# supply.net
KiCad netlist of a schematic drawn in Altium Designer
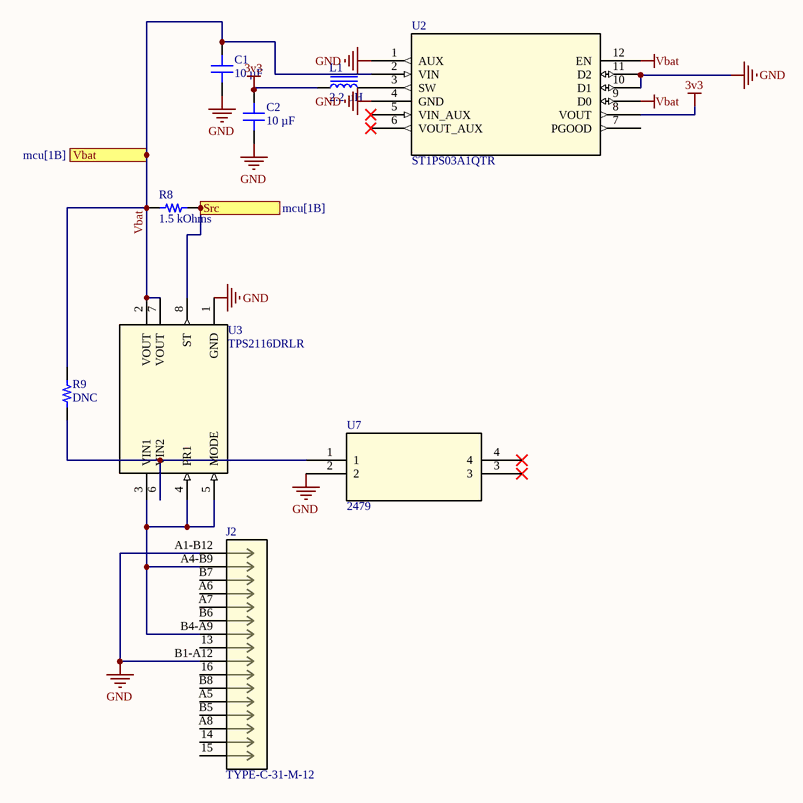
[diagram p0: supply.SchDoc]

(export (version "E")
  (design (tool "Eeschema 10.0.6"))
  (components
    (comp (ref "C1")
      (value "10 µF")
      (footprint "CAP 0402_1005")
      (description "CAP CER 0.1UF 4V X5R 0402")
      (fields (field (name "PART NUMBER") "C0402C104K7PAC7867") (field (name "MANUFACTURER") "KEMET"))
      (libsource (lib "Celestial Altium Library - altium_library") (part "Capacitor"))
    )
    (comp (ref "C2")
      (value "10 µF")
      (footprint "CAP 0402_1005")
      (description "CAP CER 0.1UF 4V X5R 0402")
      (fields (field (name "PART NUMBER") "C0402C104K7PAC7867") (field (name "MANUFACTURER") "KEMET"))
      (libsource (lib "Celestial Altium Library - altium_library") (part "Capacitor"))
    )
    (comp (ref "J2")
      (value "TYPE-C-31-M-12")
      (footprint "CONN12_C-31-M-12_HRO")
      (description "No Description Available")
      (libsource (lib "TYPE-C-31-M-12") (part "TYPE-C-31-M-12"))
    )
    (comp (ref "L1")
      (value "2.2 µH")
      (footprint "TDK VLS201612CX")
      (description "FIXED IND 6.8UH 930MA 368MOHM SM")
      (fields
        (field (name "PART NUMBER") "VLS201612CX-6R8M-1")
        (field (name "MANUFACTURER") "TDK Corporation")
      )
      (libsource (lib "Celestial Altium Library - altium_library") (part "Inductor"))
    )
    (comp (ref "R8")
      (value "1.5 kOhms")
      (footprint "RES 0402_1005")
      (description "RES 1.5K OHM 0.05% 1/10W 0402")
      (fields
        (field (name "PART NUMBER") "ERA-2VRW1501X")
        (field (name "MANUFACTURER") "Panasonic Electronic Components")
      )
      (libsource (lib "Celestial Altium Library - altium_library") (part "Resistor"))
    )
    (comp (ref "R9")
      (value "DNC")
      (footprint "RES 0402_1005")
      (description "RES 1.5K OHM 0.05% 1/10W 0402")
      (fields
        (field (name "PART NUMBER") "ERA-2VRW1501X")
        (field (name "MANUFACTURER") "Panasonic Electronic Components")
      )
      (libsource (lib "Celestial Altium Library - altium_library") (part "Resistor"))
    )
    (comp (ref "U2")
      (value "ST1PS03A1QTR")
      (footprint "TQFN12_2X1P7_STM")
      (description "No Description Available")
      (libsource (lib "ST1PS03A1QTR") (part "ST1PS03A1QTR"))
    )
    (comp (ref "U3")
      (value "TPS2116DRLR")
      (footprint "DRL0008A-MFG")
      (description "No Description Available")
      (libsource (lib "TPS2116DRLR") (part "TPS2116DRLR"))
    )
    (comp (ref "U7")
      (value "2479")
      (footprint "2479PCB_37P49X52P63_KEY")
      (description "No Description Available")
      (libsource (lib "2479") (part "2479"))
    )
  )
  (nets
    (net (code "1") (name "/Src") (class "Default")
      (node (ref "R8") (pin "1") (pinfunction "1_1") (pintype "passive"))
      (node (ref "U3") (pin "8") (pinfunction "ST_8") (pintype "output"))
    )
    (net (code "2") (name "3v3") (class "Default")
      (node (ref "C2") (pin "1") (pinfunction "1_1") (pintype "passive"))
      (node (ref "L1") (pin "1") (pinfunction "1_1") (pintype "passive"))
      (node (ref "U2") (pin "8") (pinfunction "VOUT_8") (pintype "output"))
    )
    (net (code "3") (name "GND") (class "Default")
      (node (ref "C1") (pin "2") (pinfunction "2_2") (pintype "passive"))
      (node (ref "C2") (pin "2") (pinfunction "2_2") (pintype "passive"))
      (node (ref "J2") (pin "A1-B12") (pinfunction "A1-B12_A1-B12") (pintype "passive"))
      (node (ref "J2") (pin "B1-A12") (pinfunction "B1-A12_B1-A12") (pintype "passive"))
      (node (ref "U2") (pin "1") (pinfunction "AUX_1") (pintype "output"))
      (node (ref "U2") (pin "10") (pinfunction "D1_10") (pintype "bidirectional"))
      (node (ref "U2") (pin "11") (pinfunction "D2_11") (pintype "bidirectional"))
      (node (ref "U2") (pin "4") (pinfunction "GND_4") (pintype "power_in"))
      (node (ref "U3") (pin "1") (pinfunction "GND_1") (pintype "power_in"))
      (node (ref "U7") (pin "2") (pinfunction "2_2") (pintype "passive"))
    )
    (net (code "4") (name "Net-(U2-SW)") (class "Default")
      (node (ref "L1") (pin "2") (pinfunction "2_2") (pintype "passive"))
      (node (ref "U2") (pin "3") (pinfunction "SW_3") (pintype "output"))
    )
    (net (code "5") (name "Net-(U3-MODE)") (class "Default")
      (node (ref "J2") (pin "A4-B9") (pinfunction "A4-B9_A4-B9") (pintype "passive"))
      (node (ref "J2") (pin "B4-A9") (pinfunction "B4-A9_B4-A9") (pintype "passive"))
      (node (ref "U3") (pin "3") (pinfunction "VIN1_3") (pintype "power_in"))
      (node (ref "U3") (pin "4") (pinfunction "PR1_4") (pintype "input"))
      (node (ref "U3") (pin "5") (pinfunction "MODE_5") (pintype "input"))
    )
    (net (code "6") (name "Net-(U3-VIN2)") (class "Default")
      (node (ref "R9") (pin "2") (pinfunction "2_2") (pintype "passive"))
      (node (ref "U3") (pin "6") (pinfunction "VIN2_6") (pintype "power_in"))
      (node (ref "U7") (pin "1") (pinfunction "1_1") (pintype "passive"))
    )
    (net (code "7") (name "Vbat") (class "Default")
      (node (ref "C1") (pin "1") (pinfunction "1_1") (pintype "passive"))
      (node (ref "R8") (pin "2") (pinfunction "2_2") (pintype "passive"))
      (node (ref "R9") (pin "1") (pinfunction "1_1") (pintype "passive"))
      (node (ref "U2") (pin "12") (pinfunction "EN_12") (pintype "passive"))
      (node (ref "U2") (pin "2") (pinfunction "VIN_2") (pintype "input"))
      (node (ref "U2") (pin "9") (pinfunction "D0_9") (pintype "bidirectional"))
      (node (ref "U3") (pin "2") (pinfunction "VOUT_2") (pintype "passive"))
      (node (ref "U3") (pin "7") (pinfunction "VOUT_7") (pintype "passive"))
    )
    (net (code "8") (name "unconnected-(J2-Pad13)") (class "Default")
      (node (ref "J2") (pin "13") (pinfunction "13_13") (pintype "passive"))
    )
    (net (code "9") (name "unconnected-(J2-Pad14)") (class "Default")
      (node (ref "J2") (pin "14") (pinfunction "14_14") (pintype "passive"))
    )
    (net (code "10") (name "unconnected-(J2-Pad15)") (class "Default")
      (node (ref "J2") (pin "15") (pinfunction "15_15") (pintype "passive"))
    )
    (net (code "11") (name "unconnected-(J2-Pad16)") (class "Default")
      (node (ref "J2") (pin "16") (pinfunction "16_16") (pintype "passive"))
    )
    (net (code "12") (name "unconnected-(J2-PadA5)") (class "Default")
      (node (ref "J2") (pin "A5") (pinfunction "A5_A5") (pintype "passive"))
    )
    (net (code "13") (name "unconnected-(J2-PadA6)") (class "Default")
      (node (ref "J2") (pin "A6") (pinfunction "A6_A6") (pintype "passive"))
    )
    (net (code "14") (name "unconnected-(J2-PadA7)") (class "Default")
      (node (ref "J2") (pin "A7") (pinfunction "A7_A7") (pintype "passive"))
    )
    (net (code "15") (name "unconnected-(J2-PadA8)") (class "Default")
      (node (ref "J2") (pin "A8") (pinfunction "A8_A8") (pintype "passive"))
    )
    (net (code "16") (name "unconnected-(J2-PadB5)") (class "Default")
      (node (ref "J2") (pin "B5") (pinfunction "B5_B5") (pintype "passive"))
    )
    (net (code "17") (name "unconnected-(J2-PadB6)") (class "Default")
      (node (ref "J2") (pin "B6") (pinfunction "B6_B6") (pintype "passive"))
    )
    (net (code "18") (name "unconnected-(J2-PadB7)") (class "Default")
      (node (ref "J2") (pin "B7") (pinfunction "B7_B7") (pintype "passive"))
    )
    (net (code "19") (name "unconnected-(J2-PadB8)") (class "Default")
      (node (ref "J2") (pin "B8") (pinfunction "B8_B8") (pintype "passive"))
    )
    (net (code "20") (name "unconnected-(U2-PGOOD-Pad7)") (class "Default")
      (node (ref "U2") (pin "7") (pinfunction "PGOOD_7") (pintype "output"))
    )
    (net (code "21") (name "unconnected-(U2-VIN_AUX-Pad5)") (class "Default")
      (node (ref "U2") (pin "5") (pinfunction "VIN_AUX_5") (pintype "input+no_connect"))
    )
    (net (code "22") (name "unconnected-(U2-VOUT_AUX-Pad6)") (class "Default")
      (node (ref "U2") (pin "6") (pinfunction "VOUT_AUX_6") (pintype "output+no_connect"))
    )
    (net (code "23") (name "unconnected-(U7-Pad3)") (class "Default")
      (node (ref "U7") (pin "3") (pinfunction "3_3") (pintype "passive+no_connect"))
    )
    (net (code "24") (name "unconnected-(U7-Pad4)") (class "Default")
      (node (ref "U7") (pin "4") (pinfunction "4_4") (pintype "passive+no_connect"))
    )
  )
)
